# PlacaM_e_Raw.net
KiCad netlist of a schematic drawn in Altium Designer
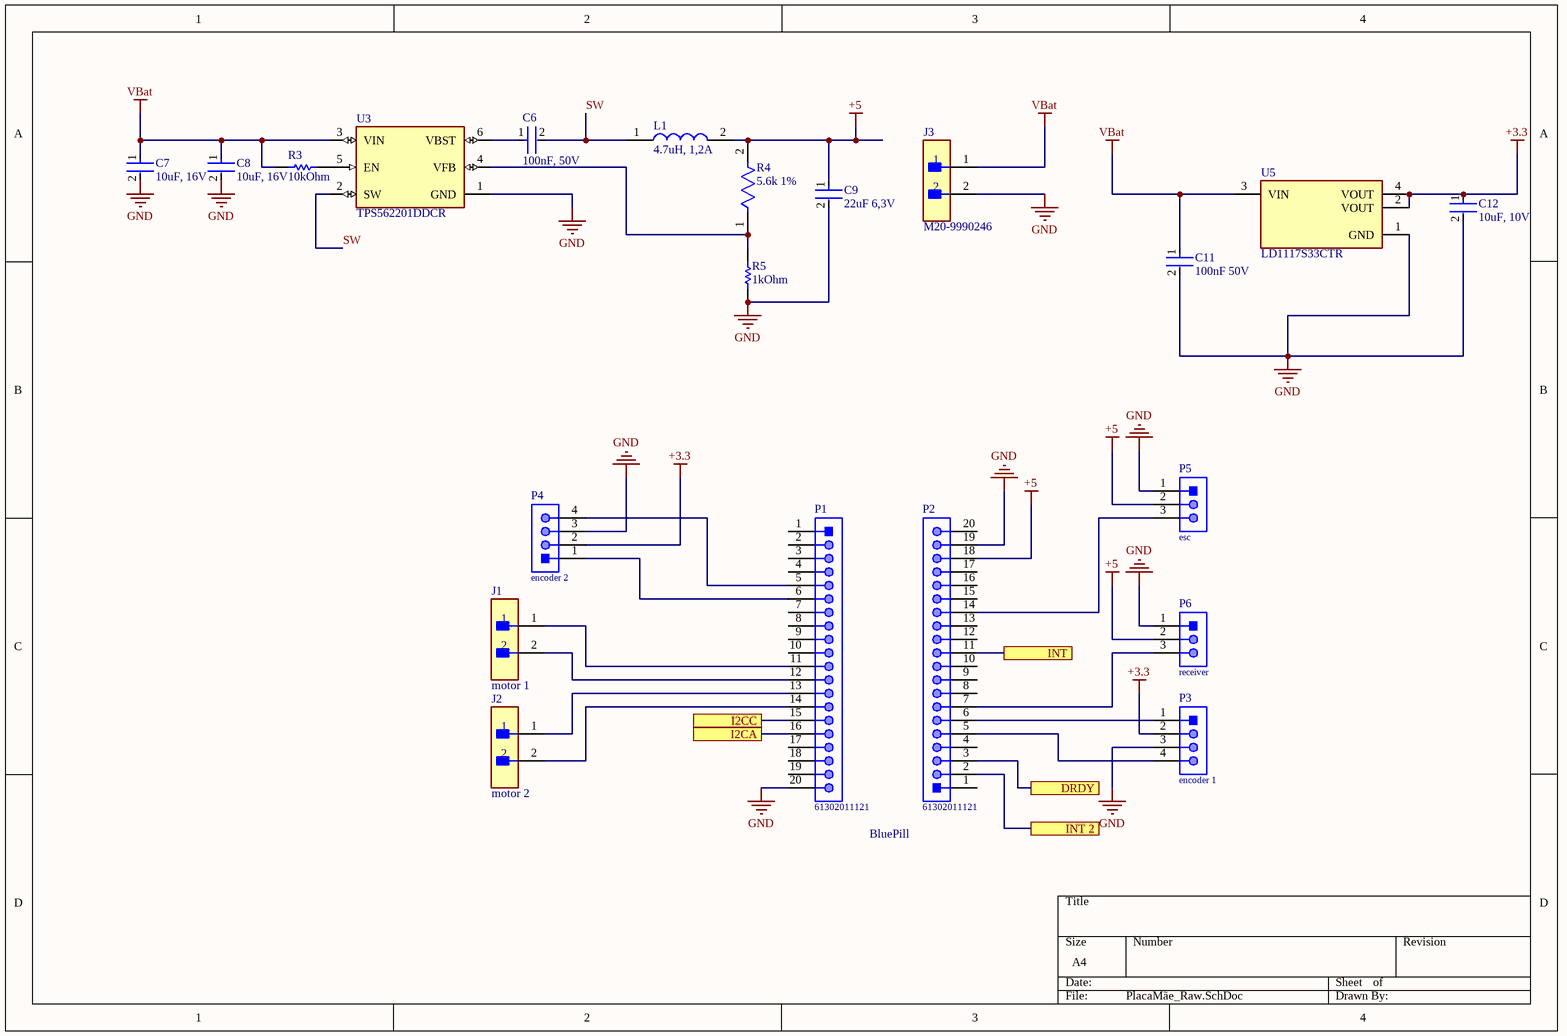
[diagram p0: PlacaMãe_Raw.SchDoc]

(export (version "E")
  (design (tool "Eeschema 10.0.6"))
  (components
    (comp (ref "C6")
      (value "100nF, 50V")
      (footprint "FP-CGA3E-0_3-0_1-IPC_A")
      (description "Cap Ceramic 100nF 50V X7R 10% Pad SMD 0603 +125°C Automotive T/R")
      (fields (field (name "TOLERANCE") "10%") (field (name "VOLTAGE") "50V"))
      (libsource (lib "Altium Content Vault") (part "b4654b650e69147ec39a6b967a45e02"))
    )
    (comp (ref "C7")
      (value "10uF, 16V")
      (footprint "FP-GRM21B-0_1-IPC_C")
      (description "Chip Multilayer Ceramic Capacitors for General Purpose, 0805, 10uF, X5R, 15%, 10%, 16V")
      (fields (field (name "TOLERANCE") "10%") (field (name "VOLTAGE") "16V"))
      (libsource (lib "Altium Content Vault") (part "b4654b650e69147ec39a6b967a45e02"))
    )
    (comp (ref "C8")
      (value "10uF, 16V")
      (footprint "FP-GRM21B-0_1-IPC_C")
      (description "Chip Multilayer Ceramic Capacitors for General Purpose, 0805, 10uF, X5R, 15%, 10%, 16V")
      (fields (field (name "TOLERANCE") "10%") (field (name "VOLTAGE") "16V"))
      (libsource (lib "Altium Content Vault") (part "b4654b650e69147ec39a6b967a45e02"))
    )
    (comp (ref "C9")
      (value "22uF 6,3V")
      (footprint "FP-GRM21B-0_15-MFG")
      (description "Chip Multilayer Ceramic Capacitors for General Purpose, 0805, 22uF, X5R, 15%, 20%, 6.3V")
      (fields (field (name "VOLTAGE") "6.3V") (field (name "TOLERANCE") "20%"))
      (libsource (lib "Altium Content Vault") (part "b4654b650e69147ec39a6b967a45e02"))
    )
    (comp (ref "C11")
      (value "100nF 50V")
      (footprint "FP-C0805C-DN-MFG")
      (description "CAP CER 0.1UF 50V X7R 0805")
      (fields
        (field (name "MANUFACTURER PART NUMBER") "C0805C104K5RACTU")
        (field (name "MANUFACTURER") "KEMET")
      )
      (libsource (lib "Altium Content Vault") (part "b4654b650e69147ec39a6b967a45e02"))
    )
    (comp (ref "C12")
      (value "10uF, 10V")
      (footprint "FP-C1608-080-MFG")
      (description "CAP CER 10UF 10V X5R 0603")
      (fields
        (field (name "MANUFACTURER PART NUMBER") "C1608X5R1A106K080AC")
        (field (name "OCTOPART") "https://octopart.com/c1608x5r1a106k080ac-tdk-26013468")
      )
      (libsource (lib "Altium Content Vault") (part "11868f565c42a9108669ba33697ecf6"))
    )
    (comp (ref "J1")
      (value "motor 1")
      (footprint "FP-M20-9990246-MFG")
      (description "CONN HEADER VERT 2POS 2.54MM")
      (fields
        (field (name "OCTOPART") "https://octopart.com/m20-9990246-harwin-2590635")
        (field (name "MANUFACTURER") "Harwin")
      )
      (libsource (lib "Altium Content Vault") (part "3bc925449376181038e59eaffc5286c"))
    )
    (comp (ref "J2")
      (value "motor 2")
      (footprint "FP-M20-9990246-MFG")
      (description "CONN HEADER VERT 2POS 2.54MM")
      (fields
        (field (name "OCTOPART") "https://octopart.com/m20-9990246-harwin-2590635")
        (field (name "MANUFACTURER") "Harwin")
      )
      (libsource (lib "Altium Content Vault") (part "3bc925449376181038e59eaffc5286c"))
    )
    (comp (ref "J3")
      (value "M20-9990246")
      (footprint "FP-M20-9990246-MFG")
      (description "CONN HEADER VERT 2POS 2.54MM")
      (fields
        (field (name "OCTOPART") "https://octopart.com/m20-9990246-harwin-2590635")
        (field (name "MANUFACTURER") "Harwin")
      )
      (libsource (lib "Altium Content Vault") (part "3bc925449376181038e59eaffc5286c"))
    )
    (comp (ref "L1")
      (value "4.7uH, 1,2A")
      (footprint "SamacSys:CDRH2D09NP4R7MC")
      (description "Inductor")
      (fields
        (field (name "MANUFACTURER_PART_NUMBER") "CDRH2D18/HPNP-4R7NC")
        (field (name "MOUSER PART NUMBER") "851-CDRH2D18HP-4R7NC")
      )
      (libsource (lib "*") (part "CDRH2D18_HPNP-4R7NC"))
    )
    (comp (ref "P1")
      (value "61302011121")
      (footprint "61302011121")
      (description "THT Vertical Pin Header WR-PHD, Pitch 2.54 mm, Single Row, 20 pins")
      (fields (field (name "MANUFACTURER") "Wurth Elektronik") (field (name "PUBLISHER") "WurthElektronik"))
      (libsource (lib "Altium Content Vault") (part "WE-CN-1P-M-R20"))
    )
    (comp (ref "P2")
      (value "61302011121")
      (footprint "61302011121")
      (description "THT Vertical Pin Header WR-PHD, Pitch 2.54 mm, Single Row, 20 pins")
      (fields (field (name "MANUFACTURER") "Wurth Elektronik") (field (name "PUBLISHER") "WurthElektronik"))
      (libsource (lib "Altium Content Vault") (part "WE-CN-1P-M-R20"))
    )
    (comp (ref "P3")
      (value "encoder 1")
      (footprint "61300411121")
      (description "THT Vertical Pin Header WR-PHD, Pitch 2.54 mm, Single Row, 4 pins")
      (fields
        (field (name "MANUFACTURER") "Wurth Elektronik")
        (field (name "PART NUMBER") "61300411121")
        (field (name "PUBLISHER") "WurthElektronik")
      )
      (libsource (lib "Altium Content Vault") (part "WE-CN-1P-M-R4"))
    )
    (comp (ref "P4")
      (value "encoder 2")
      (footprint "61300411121")
      (description "THT Vertical Pin Header WR-PHD, Pitch 2.54 mm, Single Row, 4 pins")
      (fields
        (field (name "MANUFACTURER") "Wurth Elektronik")
        (field (name "PART NUMBER") "61300411121")
        (field (name "PUBLISHER") "WurthElektronik")
      )
      (libsource (lib "") (part "WE-CN-1P-M-R4_1"))
    )
    (comp (ref "P5")
      (value "esc")
      (footprint "61300311121")
      (description "THT Vertical Pin Header WR-PHD, Pitch 2.54 mm, Single Row, 3 pins")
      (fields
        (field (name "PART NUMBER") "61300311121")
        (field (name "MANUFACTURER") "Wurth Elektronik")
        (field (name "PUBLISHER") "WurthElektronik")
      )
      (libsource (lib "Altium Content Vault") (part "WE-CN-1P-M-R3"))
    )
    (comp (ref "P6")
      (value "receiver")
      (footprint "61300311121")
      (description "THT Vertical Pin Header WR-PHD, Pitch 2.54 mm, Single Row, 3 pins")
      (fields
        (field (name "PART NUMBER") "61300311121")
        (field (name "MANUFACTURER") "Wurth Elektronik")
        (field (name "PUBLISHER") "WurthElektronik")
      )
      (libsource (lib "Altium Content Vault") (part "WE-CN-1P-M-R3"))
    )
    (comp (ref "R3")
      (value "10kOhm")
      (footprint "RESC1609X55X30LL15T15")
      (description "Chip Resistor, 10 KOhm, +/- 1%, 0.1 W, -55 to 155 degC, 0603 (1608 Metric), RoHS, Tape and Reel")
      (fields (field (name "TOLERANCE") "1%") (field (name "MANUFACTURER") "Panasonic"))
      (libsource (lib "Altium Content Vault") (part "RES-2"))
    )
    (comp (ref "R4")
      (value "5.6k 1%")
      (footprint "FP-CRCW0805-e3-IPC_A")
      (description "RES Thick Film, 5.6kΩ, 1%, 0.125W, 100ppm/°C, 0805")
      (fields (field (name "TOLERANCE") "1%"))
      (libsource (lib "Altium Content Vault") (part "1029c3af85768c4190bb7ad29bc67b5"))
    )
    (comp (ref "R5")
      (value "1kOhm")
      (footprint "RESC1608X55X30ML20T20")
      (fields (field (name "PART NUMBER") "ERA-3AEB103V") (field (name "MANUFACTURER") "Panasonic"))
      (libsource (lib "Altium Content Vault") (part "RES"))
    )
    (comp (ref "U3")
      (value "TPS562201DDCR")
      (footprint "FP-DDC0006A-IPC_A")
      (description "IC REG BUCK ADJ 2A TSOT23-6")
      (libsource (lib "Altium Content Vault") (part "957e164956730ea4bf6293280af19fc"))
    )
    (comp (ref "U5")
      (value "LD1117S33CTR")
      (footprint "FP-SOT-223-0046067_14-MFG")
      (description "IC REG LINEAR 3.3V 800MA SOT223")
      (libsource (lib "Altium Content Vault") (part "7818869c5c16ceab15634627166a29d"))
    )
  )
  (nets
    (net (code "1") (name "+3.3") (class "Default")
      (node (ref "C12") (pin "1") (pinfunction "1_1") (pintype "passive"))
      (node (ref "P3") (pin "2") (pinfunction "2_2") (pintype "passive"))
      (node (ref "P4") (pin "2") (pinfunction "2_2") (pintype "passive"))
      (node (ref "U5") (pin "2") (pinfunction "VOUT_2") (pintype "power_in"))
      (node (ref "U5") (pin "4") (pinfunction "VOUT_4") (pintype "power_in"))
    )
    (net (code "2") (name "+5") (class "Default")
      (node (ref "C9") (pin "1") (pinfunction "1_1") (pintype "passive"))
      (node (ref "L1") (pin "2") (pinfunction "2_2") (pintype "passive"))
      (node (ref "P2") (pin "18") (pinfunction "18_18") (pintype "passive"))
      (node (ref "P5") (pin "2") (pinfunction "2_2") (pintype "passive"))
      (node (ref "P6") (pin "2") (pinfunction "2_2") (pintype "passive"))
      (node (ref "R4") (pin "2") (pinfunction "2_2") (pintype "passive"))
    )
    (net (code "3") (name "/DRDY") (class "Default")
      (node (ref "P2") (pin "3") (pinfunction "3_3") (pintype "passive"))
    )
    (net (code "4") (name "/I2CA") (class "Default")
      (node (ref "P1") (pin "16") (pinfunction "16_16") (pintype "passive"))
    )
    (net (code "5") (name "/I2CC") (class "Default")
      (node (ref "P1") (pin "15") (pinfunction "15_15") (pintype "passive"))
    )
    (net (code "6") (name "/INT") (class "Default")
      (node (ref "P2") (pin "11") (pinfunction "11_11") (pintype "passive"))
    )
    (net (code "7") (name "/INT 2") (class "Default")
      (node (ref "P2") (pin "2") (pinfunction "2_2") (pintype "passive"))
    )
    (net (code "8") (name "/SW") (class "Default")
      (node (ref "C6") (pin "2") (pinfunction "2_2") (pintype "passive"))
      (node (ref "L1") (pin "1") (pinfunction "1_1") (pintype "passive"))
      (node (ref "U3") (pin "2") (pinfunction "SW_2") (pintype "bidirectional"))
    )
    (net (code "9") (name "GND") (class "Default")
      (node (ref "C11") (pin "2") (pinfunction "2_2") (pintype "passive"))
      (node (ref "C12") (pin "2") (pinfunction "2_2") (pintype "passive"))
      (node (ref "C7") (pin "2") (pinfunction "2_2") (pintype "passive"))
      (node (ref "C8") (pin "2") (pinfunction "2_2") (pintype "passive"))
      (node (ref "C9") (pin "2") (pinfunction "2_2") (pintype "passive"))
      (node (ref "J3") (pin "2") (pinfunction "2_2") (pintype "passive"))
      (node (ref "P1") (pin "20") (pinfunction "20_20") (pintype "passive"))
      (node (ref "P2") (pin "19") (pinfunction "19_19") (pintype "passive"))
      (node (ref "P3") (pin "3") (pinfunction "3_3") (pintype "passive"))
      (node (ref "P4") (pin "3") (pinfunction "3_3") (pintype "passive"))
      (node (ref "P5") (pin "1") (pinfunction "1_1") (pintype "passive"))
      (node (ref "P6") (pin "1") (pinfunction "1_1") (pintype "passive"))
      (node (ref "R5") (pin "1") (pinfunction "1_1") (pintype "passive"))
      (node (ref "U3") (pin "1") (pinfunction "GND_1") (pintype "power_in"))
      (node (ref "U5") (pin "1") (pinfunction "GND_1") (pintype "power_in"))
    )
    (net (code "10") (name "Net-(J1-Pad1)") (class "Default")
      (node (ref "J1") (pin "1") (pinfunction "1_1") (pintype "passive"))
      (node (ref "P1") (pin "11") (pinfunction "11_11") (pintype "passive"))
    )
    (net (code "11") (name "Net-(J1-Pad2)") (class "Default")
      (node (ref "J1") (pin "2") (pinfunction "2_2") (pintype "passive"))
      (node (ref "P1") (pin "12") (pinfunction "12_12") (pintype "passive"))
    )
    (net (code "12") (name "Net-(J2-Pad1)") (class "Default")
      (node (ref "J2") (pin "1") (pinfunction "1_1") (pintype "passive"))
      (node (ref "P1") (pin "13") (pinfunction "13_13") (pintype "passive"))
    )
    (net (code "13") (name "Net-(J2-Pad2)") (class "Default")
      (node (ref "J2") (pin "2") (pinfunction "2_2") (pintype "passive"))
      (node (ref "P1") (pin "14") (pinfunction "14_14") (pintype "passive"))
    )
    (net (code "14") (name "Net-(P1-Pad5)") (class "Default")
      (node (ref "P1") (pin "5") (pinfunction "5_5") (pintype "passive"))
      (node (ref "P4") (pin "4") (pinfunction "4_4") (pintype "passive"))
    )
    (net (code "15") (name "Net-(P1-Pad6)") (class "Default")
      (node (ref "P1") (pin "6") (pinfunction "6_6") (pintype "passive"))
      (node (ref "P4") (pin "1") (pinfunction "1_1") (pintype "passive"))
    )
    (net (code "16") (name "Net-(P2-Pad5)") (class "Default")
      (node (ref "P2") (pin "5") (pinfunction "5_5") (pintype "passive"))
      (node (ref "P3") (pin "4") (pinfunction "4_4") (pintype "passive"))
    )
    (net (code "17") (name "Net-(P2-Pad6)") (class "Default")
      (node (ref "P2") (pin "6") (pinfunction "6_6") (pintype "passive"))
      (node (ref "P3") (pin "1") (pinfunction "1_1") (pintype "passive"))
    )
    (net (code "18") (name "Net-(P2-Pad7)") (class "Default")
      (node (ref "P2") (pin "7") (pinfunction "7_7") (pintype "passive"))
      (node (ref "P6") (pin "3") (pinfunction "3_3") (pintype "passive"))
    )
    (net (code "19") (name "Net-(P2-Pad14)") (class "Default")
      (node (ref "P2") (pin "14") (pinfunction "14_14") (pintype "passive"))
      (node (ref "P5") (pin "3") (pinfunction "3_3") (pintype "passive"))
    )
    (net (code "20") (name "Net-(U3-EN)") (class "Default")
      (node (ref "R3") (pin "2") (pinfunction "2_2") (pintype "passive"))
      (node (ref "U3") (pin "5") (pinfunction "EN_5") (pintype "input"))
    )
    (net (code "21") (name "Net-(U3-VBST)") (class "Default")
      (node (ref "C6") (pin "1") (pinfunction "1_1") (pintype "passive"))
      (node (ref "U3") (pin "6") (pinfunction "VBST_6") (pintype "bidirectional"))
    )
    (net (code "22") (name "Net-(U3-VFB)") (class "Default")
      (node (ref "R4") (pin "1") (pinfunction "1_1") (pintype "passive"))
      (node (ref "R5") (pin "2") (pinfunction "2_2") (pintype "passive"))
      (node (ref "U3") (pin "4") (pinfunction "VFB_4") (pintype "bidirectional"))
    )
    (net (code "23") (name "VBat") (class "Default")
      (node (ref "C11") (pin "1") (pinfunction "1_1") (pintype "passive"))
      (node (ref "C7") (pin "1") (pinfunction "1_1") (pintype "passive"))
      (node (ref "C8") (pin "1") (pinfunction "1_1") (pintype "passive"))
      (node (ref "J3") (pin "1") (pinfunction "1_1") (pintype "passive"))
      (node (ref "R3") (pin "1") (pinfunction "1_1") (pintype "passive"))
      (node (ref "U3") (pin "3") (pinfunction "VIN_3") (pintype "bidirectional"))
      (node (ref "U5") (pin "3") (pinfunction "VIN_3") (pintype "power_in"))
    )
    (net (code "24") (name "unconnected-(P1-Pad1)") (class "Default")
      (node (ref "P1") (pin "1") (pinfunction "1_1") (pintype "passive"))
    )
    (net (code "25") (name "unconnected-(P1-Pad2)") (class "Default")
      (node (ref "P1") (pin "2") (pinfunction "2_2") (pintype "passive"))
    )
    (net (code "26") (name "unconnected-(P1-Pad3)") (class "Default")
      (node (ref "P1") (pin "3") (pinfunction "3_3") (pintype "passive"))
    )
    (net (code "27") (name "unconnected-(P1-Pad4)") (class "Default")
      (node (ref "P1") (pin "4") (pinfunction "4_4") (pintype "passive"))
    )
    (net (code "28") (name "unconnected-(P1-Pad7)") (class "Default")
      (node (ref "P1") (pin "7") (pinfunction "7_7") (pintype "passive"))
    )
    (net (code "29") (name "unconnected-(P1-Pad8)") (class "Default")
      (node (ref "P1") (pin "8") (pinfunction "8_8") (pintype "passive"))
    )
    (net (code "30") (name "unconnected-(P1-Pad9)") (class "Default")
      (node (ref "P1") (pin "9") (pinfunction "9_9") (pintype "passive"))
    )
    (net (code "31") (name "unconnected-(P1-Pad10)") (class "Default")
      (node (ref "P1") (pin "10") (pinfunction "10_10") (pintype "passive"))
    )
    (net (code "32") (name "unconnected-(P1-Pad17)") (class "Default")
      (node (ref "P1") (pin "17") (pinfunction "17_17") (pintype "passive"))
    )
    (net (code "33") (name "unconnected-(P1-Pad18)") (class "Default")
      (node (ref "P1") (pin "18") (pinfunction "18_18") (pintype "passive"))
    )
    (net (code "34") (name "unconnected-(P1-Pad19)") (class "Default")
      (node (ref "P1") (pin "19") (pinfunction "19_19") (pintype "passive"))
    )
    (net (code "35") (name "unconnected-(P2-Pad1)") (class "Default")
      (node (ref "P2") (pin "1") (pinfunction "1_1") (pintype "passive"))
    )
    (net (code "36") (name "unconnected-(P2-Pad4)") (class "Default")
      (node (ref "P2") (pin "4") (pinfunction "4_4") (pintype "passive"))
    )
    (net (code "37") (name "unconnected-(P2-Pad8)") (class "Default")
      (node (ref "P2") (pin "8") (pinfunction "8_8") (pintype "passive"))
    )
    (net (code "38") (name "unconnected-(P2-Pad9)") (class "Default")
      (node (ref "P2") (pin "9") (pinfunction "9_9") (pintype "passive"))
    )
    (net (code "39") (name "unconnected-(P2-Pad10)") (class "Default")
      (node (ref "P2") (pin "10") (pinfunction "10_10") (pintype "passive"))
    )
    (net (code "40") (name "unconnected-(P2-Pad12)") (class "Default")
      (node (ref "P2") (pin "12") (pinfunction "12_12") (pintype "passive"))
    )
    (net (code "41") (name "unconnected-(P2-Pad13)") (class "Default")
      (node (ref "P2") (pin "13") (pinfunction "13_13") (pintype "passive"))
    )
    (net (code "42") (name "unconnected-(P2-Pad15)") (class "Default")
      (node (ref "P2") (pin "15") (pinfunction "15_15") (pintype "passive"))
    )
    (net (code "43") (name "unconnected-(P2-Pad16)") (class "Default")
      (node (ref "P2") (pin "16") (pinfunction "16_16") (pintype "passive"))
    )
    (net (code "44") (name "unconnected-(P2-Pad17)") (class "Default")
      (node (ref "P2") (pin "17") (pinfunction "17_17") (pintype "passive"))
    )
    (net (code "45") (name "unconnected-(P2-Pad20)") (class "Default")
      (node (ref "P2") (pin "20") (pinfunction "20_20") (pintype "passive"))
    )
  )
)
